# gate-emitter.net
KiCad netlist of a schematic drawn in EAGLE
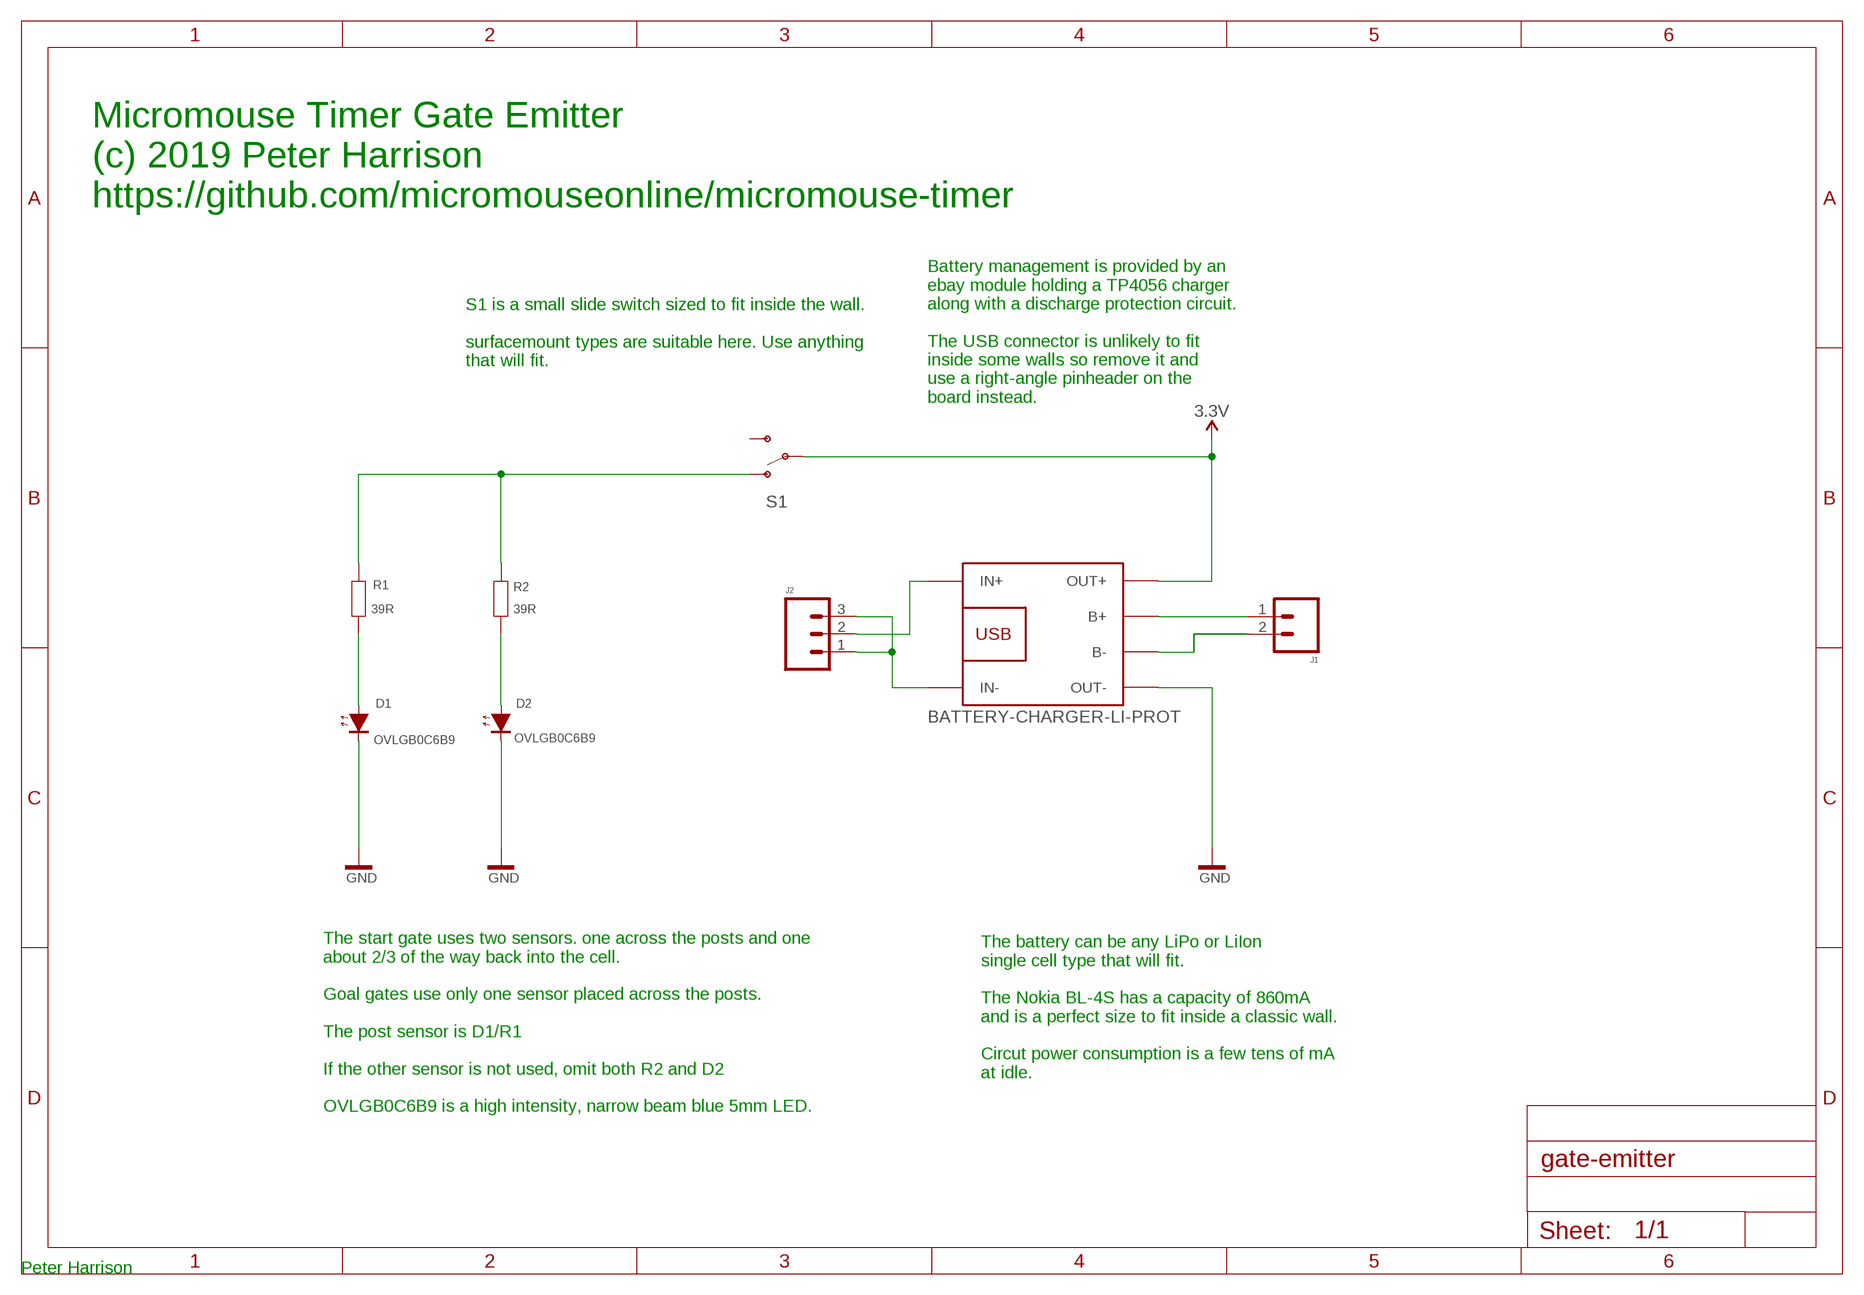
[diagram p0: schematic, sheet 1]

(export (version "E")
  (design (tool "Eeschema 10.0.6"))
  (components
    (comp (ref "D1")
      (value "OVLGB0C6B9")
      (footprint "eagle-import:LED5MM-H")
      (libsource (lib "eagle-import") (part "LED"))
    )
    (comp (ref "D2")
      (value "OVLGB0C6B9")
      (footprint "eagle-import:LED5MM-H")
      (libsource (lib "eagle-import") (part "LED"))
    )
    (comp (ref "J1")
      (value "M02RA_MALE_MILL")
      (footprint "eagle-import:1X02_RA_PTH_MALE_MILL")
      (libsource (lib "eagle-import") (part "M02RA_MALE_MILL"))
    )
    (comp (ref "J2")
      (value "M03RA_MALE")
      (footprint "eagle-import:1X03_RA_PTH_MILL")
      (libsource (lib "eagle-import") (part "M03RA_MALE"))
    )
    (comp (ref "R1")
      (value "39R")
      (footprint "eagle-import:AXIAL-0207_0.4")
      (libsource (lib "eagle-import") (part "RESISTOR_AXIAL-0207_0.4"))
    )
    (comp (ref "R2")
      (value "39R")
      (footprint "eagle-import:AXIAL-0207_0.4")
      (libsource (lib "eagle-import") (part "RESISTOR_AXIAL-0207_0.4"))
    )
    (comp (ref "S1")
      (value "SWITCH-SPDT-PTH-11.6X4.0MM")
      (footprint "eagle-import:SWITCH_SPDT_PTH_11.6X4.0MM")
      (libsource (lib "eagle-import") (part "SWITCH-SPDT-PTH-11.6X4.0MM"))
    )
    (comp (ref "U$2")
      (value "BATTERY-CHARGER-LI-PROT")
      (footprint "eagle-import:BATTERY-CHARGER-LI-PROT")
      (libsource (lib "eagle-import") (part "BATTERY-CHARGER-LI-PROT"))
    )
  )
  (nets
    (net (code "1") (name "3.3V") (class "Default")
      (node (ref "S1") (pin "2") (pinfunction "P_2") (pintype "passive"))
      (node (ref "U$2") (pin "OUT+") (pinfunction "OUT+_OUT+") (pintype "bidirectional"))
    )
    (net (code "2") (name "GND") (class "Default")
      (node (ref "D1") (pin "C") (pinfunction "C_C") (pintype "passive"))
      (node (ref "D2") (pin "C") (pinfunction "C_C") (pintype "passive"))
      (node (ref "U$2") (pin "OUT-") (pinfunction "OUT-_OUT-") (pintype "bidirectional"))
    )
    (net (code "3") (name "Net-(D1-PadA)") (class "Default")
      (node (ref "D1") (pin "A") (pinfunction "A_A") (pintype "passive"))
      (node (ref "R1") (pin "1") (pinfunction "1_1") (pintype "passive"))
    )
    (net (code "4") (name "Net-(D2-PadA)") (class "Default")
      (node (ref "D2") (pin "A") (pinfunction "A_A") (pintype "passive"))
      (node (ref "R2") (pin "1") (pinfunction "1_1") (pintype "passive"))
    )
    (net (code "5") (name "Net-(J1-Pad1)") (class "Default")
      (node (ref "J1") (pin "1") (pinfunction "1_1") (pintype "passive"))
      (node (ref "U$2") (pin "B+") (pinfunction "B+_B+") (pintype "bidirectional"))
    )
    (net (code "6") (name "Net-(J1-Pad2)") (class "Default")
      (node (ref "J1") (pin "2") (pinfunction "2_2") (pintype "passive"))
      (node (ref "U$2") (pin "B-") (pinfunction "B-_B-") (pintype "bidirectional"))
    )
    (net (code "7") (name "Net-(J2-Pad1)") (class "Default")
      (node (ref "J2") (pin "1") (pinfunction "1_1") (pintype "passive"))
      (node (ref "J2") (pin "3") (pinfunction "3_3") (pintype "passive"))
      (node (ref "U$2") (pin "IN-") (pinfunction "IN-_IN-") (pintype "bidirectional"))
    )
    (net (code "8") (name "Net-(J2-Pad2)") (class "Default")
      (node (ref "J2") (pin "2") (pinfunction "2_2") (pintype "passive"))
      (node (ref "U$2") (pin "IN+") (pinfunction "IN+_IN+") (pintype "bidirectional"))
    )
    (net (code "9") (name "Net-(S1-O)") (class "Default")
      (node (ref "R1") (pin "2") (pinfunction "2_2") (pintype "passive"))
      (node (ref "R2") (pin "2") (pinfunction "2_2") (pintype "passive"))
      (node (ref "S1") (pin "1") (pinfunction "O_1") (pintype "passive"))
    )
    (net (code "10") (name "unconnected-(S1-S-Pad3)") (class "Default")
      (node (ref "S1") (pin "3") (pinfunction "S_3") (pintype "passive"))
    )
  )
)
